# attac_decay_generator.net
KiCad netlist of a schematic drawn in Altium Designer
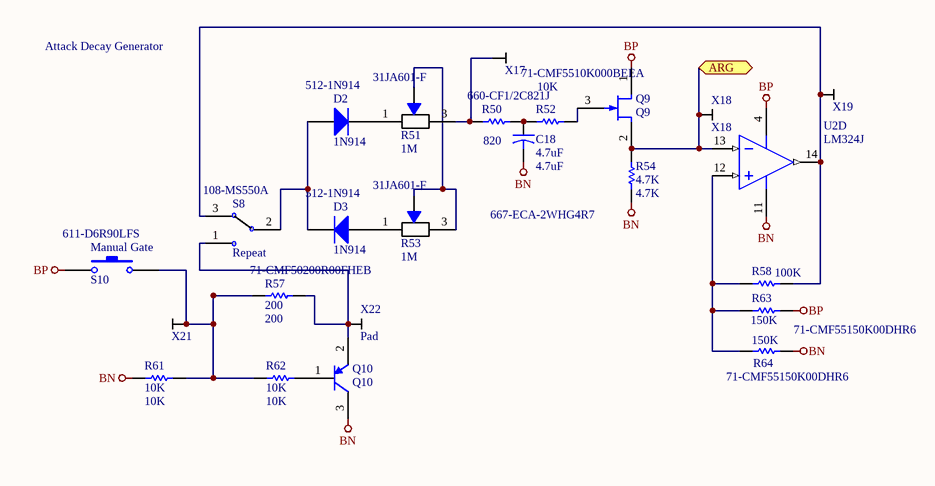
[diagram p0: attac_decay_generator.SchDoc]

(export (version "E")
  (design (tool "Eeschema 10.0.6"))
  (components
    (comp (ref "C18")
      (value "4.7uF")
      (footprint "CAPR5-4X5")
      (description "Capacitor")
      (fields
        (field (name "ALTIUM_VALUE") "4.7uF")
        (field (name "SUPPLIER PART NUMBER 1") "667-ECA-2WHG4R7")
        (field (name "MANUFACTURER") "Panasonic")
        (field (name "MANUFACTURER PART NUMBER") "ECA-2WHG4R7")
        (field (name "PUBLISHER") "Altium Limited")
      )
      (libsource (lib "Miscellaneous Devices") (part "Cap2"))
    )
    (comp (ref "D2")
      (value "1N914")
      (footprint "DO-35")
      (description "High Conductance Fast Diode")
      (fields
        (field (name "SUPPLIER PART NUMBER 1") "512-1N914")
        (field (name "MANUFACTURER") "ON Semiconductor / Fairchild")
        (field (name "PUBLISHER") "Altium Limited")
      )
      (libsource (lib "Miscellaneous Devices") (part "Diode 1N914"))
    )
    (comp (ref "D3")
      (value "1N914")
      (footprint "DO-35")
      (description "High Conductance Fast Diode")
      (fields
        (field (name "SUPPLIER PART NUMBER 1") "512-1N914")
        (field (name "MANUFACTURER") "ON Semiconductor / Fairchild")
        (field (name "PUBLISHER") "Altium Limited")
      )
      (libsource (lib "Miscellaneous Devices") (part "Diode 1N914"))
    )
    (comp (ref "Manual Gate")
      (value "S10")
      (footprint "SPST-2")
      (description "Switch")
      (fields
        (field (name "SUPPLIER PART NUMBER 1") "611-D6R90LFS")
        (field (name "MANUFACTURER") "C&K Components")
        (field (name "MANUFACTURER PART NUMBER") "D6R90 F1 LFS")
        (field (name "PUBLISHER") "Altium Limited")
      )
      (libsource (lib "Miscellaneous Devices") (part "SW-PB"))
    )
    (comp (ref "Q9")
      (value "Q9")
      (footprint "ONSC-SOT-23-3-318-08_V")
      (description "JFET Switching Transistor, N-Channel, 3-Pin SOT-23, Tape and Reel")
      (fields (field (name "MANUFACTURER") "On Semiconductor") (field (name "PARTNUMBER") "MMBF4391LT1"))
      (libsource (lib "ON Semi JFETs") (part "MMBF4391LT1"))
    )
    (comp (ref "Q10")
      (value "Q10")
      (footprint "ONSC-SC-75-3-463-01_V")
      (description "General Purpose Transistor, PNP Silicon, 3-Pin SC-75, Pb-Free, Tape and Reel")
      (fields (field (name "MANUFACTURER") "On Semiconductor") (field (name "PARTNUMBER") "MMBT3906TT1G"))
      (libsource (lib "ON Semi General Purpose Transistors") (part "MMBT3906TT1G"))
    )
    (comp (ref "R50")
      (value "820")
      (footprint "AXIAL-0.3")
      (description "Resistor")
      (fields
        (field (name "SUPPLIER PART NUMBER 1") "660-CF1/2C821J")
        (field (name "MANUFACTURER") "KOA Speer")
        (field (name "MANUFACTURER PART NUMBER") "CF1/2C821J")
        (field (name "PUBLISHER") "Altium Limited")
      )
      (libsource (lib "Miscellaneous Devices") (part "Res1"))
    )
    (comp (ref "R51")
      (value "1M")
      (footprint "Potentiometer")
      (description "My Own")
      (fields
        (field (name "SUPPLIER PART NUMBER 1") "31JA601-F")
        (field (name "MANUFACTURER") "Alpha (Taiwan)")
        (field (name "MANUFACTURER PART NUMBER") "RV16AF-10-20R1-A1M-LA")
      )
      (libsource (lib "MyLibrary") (part "Potentiometer"))
    )
    (comp (ref "R52")
      (value "10K")
      (footprint "AXIAL-0.3")
      (description "Metal Film Resistors - Through Hole 1/4watt 10Kohms 5% Rated to 1/2watt")
      (fields
        (field (name "MANUFACTURER") "Vishay / Dale")
        (field (name "MANUFACTURER PART NUMBER") "CCF0710K0JKE36")
        (field (name "SUPPLIER PART NUMBER 2") "71-CMF5510K000BEEA")
        (field (name "PUBLISHER") "Altium Limited")
      )
      (libsource (lib "Miscellaneous Devices") (part "Res1"))
    )
    (comp (ref "R53")
      (value "1M")
      (footprint "Potentiometer")
      (description "My Own")
      (fields
        (field (name "SUPPLIER PART NUMBER 1") "31JA601-F")
        (field (name "MANUFACTURER") "Alpha (Taiwan)")
        (field (name "MANUFACTURER PART NUMBER") "RV16AF-10-20R1-A1M-LA")
      )
      (libsource (lib "MyLibrary") (part "Potentiometer"))
    )
    (comp (ref "R54")
      (value "4.7K")
      (footprint "AXIAL-0.3")
      (description "Resistor")
      (fields
        (field (name "ALTIUM_VALUE") "4.7K")
        (field (name "MANUFACTURER") "Vishay / Dale")
        (field (name "MANUFACTURER PART NUMBER") "CCF074K70JKE36")
        (field (name "PUBLISHER") "Altium Limited")
      )
      (libsource (lib "Miscellaneous Devices") (part "Res1"))
    )
    (comp (ref "R57")
      (value "200")
      (footprint "AXIAL-0.3")
      (description "Resistor")
      (fields
        (field (name "ALTIUM_VALUE") "200")
        (field (name "SUPPLIER PART NUMBER 1") "71-CMF50200R00FHEB")
        (field (name "MANUFACTURER") "Vishay / Dale")
        (field (name "MANUFACTURER PART NUMBER") "CMF50200R00FHEB")
        (field (name "PUBLISHER") "Altium Limited")
      )
      (libsource (lib "Miscellaneous Devices") (part "Res1"))
    )
    (comp (ref "R58")
      (value "100K")
      (footprint "AXIAL-0.3")
      (description "Resistor")
      (fields
        (field (name "MANUFACTURER") "Vishay / Dale")
        (field (name "MANUFACTURER PART NUMBER") "CMF55100K00FHEK")
        (field (name "PUBLISHER") "Altium Limited")
      )
      (libsource (lib "Miscellaneous Devices") (part "Res1"))
    )
    (comp (ref "R61")
      (value "10K")
      (footprint "AXIAL-0.3")
      (description "Metal Film Resistors - Through Hole 1/4watt 10Kohms 5% Rated to 1/2watt")
      (fields
        (field (name "ALTIUM_VALUE") "10K")
        (field (name "MANUFACTURER") "Vishay / Dale")
        (field (name "MANUFACTURER PART NUMBER") "CCF0710K0JKE36")
        (field (name "PUBLISHER") "Altium Limited")
      )
      (libsource (lib "Miscellaneous Devices") (part "Res1"))
    )
    (comp (ref "R62")
      (value "10K")
      (footprint "AXIAL-0.3")
      (description "Metal Film Resistors - Through Hole 1/4watt 10Kohms 5% Rated to 1/2watt")
      (fields
        (field (name "ALTIUM_VALUE") "10K")
        (field (name "MANUFACTURER") "Vishay / Dale")
        (field (name "MANUFACTURER PART NUMBER") "CCF0710K0JKE36")
        (field (name "PUBLISHER") "Altium Limited")
      )
      (libsource (lib "Miscellaneous Devices") (part "Res1"))
    )
    (comp (ref "R63")
      (value "150K")
      (footprint "AXIAL-0.3")
      (description "Resistor")
      (fields
        (field (name "SUPPLIER PART NUMBER 1") "71-CMF55150K00DHR6")
        (field (name "MANUFACTURER") "Vishay / Dale")
        (field (name "MANUFACTURER PART NUMBER") "CMF55150K00DHR6")
        (field (name "PUBLISHER") "Altium Limited")
      )
      (libsource (lib "Miscellaneous Devices") (part "Res1"))
    )
    (comp (ref "R64")
      (value "150K")
      (footprint "AXIAL-0.3")
      (description "Resistor")
      (fields
        (field (name "SUPPLIER PART NUMBER 1") "71-CMF55150K00DHR6")
        (field (name "MANUFACTURER") "Vishay / Dale")
        (field (name "MANUFACTURER PART NUMBER") "CMF55150K00DHR6")
        (field (name "PUBLISHER") "Altium Limited")
      )
      (libsource (lib "Miscellaneous Devices") (part "Res1"))
    )
    (comp (ref "S8")
      (value "Repeat")
      (footprint "SPDT Switch")
      (description "SPDT Switch")
      (fields
        (field (name "SUPPLIER PART NUMBER 1") "108-MS550A")
        (field (name "MANUFACTURER") "Mountain Switch")
        (field (name "MANUFACTURER PART NUMBER") "108-MS550A")
      )
      (libsource (lib "MyLibrary") (part "SPDT Switch"))
    )
    (comp (ref "U2")
      (value "LM324J")
      (footprint "J14A")
      (description "Low Power Quad Operational Amplifier, 14-pin CerDIP")
      (fields (field (name "MANUFACTURER") "National Semiconductor"))
      (libsource (lib "National Semiconductor Amplifier") (part "LM324J"))
    )
    (comp (ref "X17") (value "X17") (footprint "Pad") (libsource (lib "MyLibrary") (part "Pad")))
    (comp (ref "X18") (value "X18") (footprint "Pad") (libsource (lib "MyLibrary") (part "Pad")))
    (comp (ref "X19") (value "X19") (footprint "Pad") (libsource (lib "MyLibrary") (part "Pad")))
    (comp (ref "X21") (value "X21") (footprint "Pad") (libsource (lib "MyLibrary") (part "Pad")))
    (comp (ref "X22") (value "Pad") (footprint "Pad") (libsource (lib "MyLibrary") (part "Pad")))
  )
  (nets
    (net (code "1") (name "/ARG") (class "Default")
      (node (ref "Q9") (pin "2") (pinfunction "S_2") (pintype "passive"))
      (node (ref "R54") (pin "2") (pinfunction "2_2") (pintype "passive"))
      (node (ref "U2") (pin "13") (pinfunction "IN4-_13") (pintype "input"))
      (node (ref "X18") (pin "1") (pinfunction "1_1") (pintype "passive"))
    )
    (net (code "2") (name "BN") (class "Default")
      (node (ref "C18") (pin "2") (pinfunction "2_2") (pintype "passive"))
      (node (ref "Q10") (pin "3") (pinfunction "C_3") (pintype "passive"))
      (node (ref "R54") (pin "1") (pinfunction "1_1") (pintype "passive"))
      (node (ref "R61") (pin "1") (pinfunction "1_1") (pintype "passive"))
      (node (ref "R64") (pin "2") (pinfunction "2_2") (pintype "passive"))
      (node (ref "U2") (pin "11") (pinfunction "GND_11") (pintype "power_in"))
    )
    (net (code "3") (name "BP") (class "Default")
      (node (ref "Manual Gate") (pin "1") (pinfunction "1_1") (pintype "passive"))
      (node (ref "Q9") (pin "1") (pinfunction "D_1") (pintype "passive"))
      (node (ref "R63") (pin "2") (pinfunction "2_2") (pintype "passive"))
      (node (ref "U2") (pin "4") (pinfunction "V+_4") (pintype "power_in"))
    )
    (net (code "4") (name "Net-(C18-Pad1)") (class "Default")
      (node (ref "C18") (pin "1") (pinfunction "1_1") (pintype "passive"))
      (node (ref "R50") (pin "2") (pinfunction "2_2") (pintype "passive"))
      (node (ref "R52") (pin "1") (pinfunction "1_1") (pintype "passive"))
    )
    (net (code "5") (name "Net-(D2-A)") (class "Default")
      (node (ref "D2") (pin "1") (pinfunction "A_1") (pintype "passive"))
      (node (ref "D3") (pin "2") (pinfunction "K_2") (pintype "passive"))
      (node (ref "S8") (pin "2") (pinfunction "2_2") (pintype "passive"))
    )
    (net (code "6") (name "Net-(D2-K)") (class "Default")
      (node (ref "D2") (pin "2") (pinfunction "K_2") (pintype "passive"))
      (node (ref "R51") (pin "1") (pinfunction "1_1") (pintype "passive"))
    )
    (net (code "7") (name "Net-(D3-A)") (class "Default")
      (node (ref "D3") (pin "1") (pinfunction "A_1") (pintype "passive"))
      (node (ref "R53") (pin "1") (pinfunction "1_1") (pintype "passive"))
    )
    (net (code "8") (name "Net-(Manual Gate-Pad2)") (class "Default")
      (node (ref "Manual Gate") (pin "2") (pinfunction "2_2") (pintype "passive"))
      (node (ref "R57") (pin "1") (pinfunction "1_1") (pintype "passive"))
      (node (ref "R61") (pin "2") (pinfunction "2_2") (pintype "passive"))
      (node (ref "R62") (pin "1") (pinfunction "1_1") (pintype "passive"))
      (node (ref "X21") (pin "1") (pinfunction "1_1") (pintype "passive"))
    )
    (net (code "9") (name "Net-(Q9-G)") (class "Default")
      (node (ref "Q9") (pin "3") (pinfunction "G_3") (pintype "passive"))
      (node (ref "R52") (pin "2") (pinfunction "2_2") (pintype "passive"))
    )
    (net (code "10") (name "Net-(Q10-B)") (class "Default")
      (node (ref "Q10") (pin "1") (pinfunction "B_1") (pintype "passive"))
      (node (ref "R62") (pin "2") (pinfunction "2_2") (pintype "passive"))
    )
    (net (code "11") (name "Net-(Q10-E)") (class "Default")
      (node (ref "Q10") (pin "2") (pinfunction "E_2") (pintype "passive"))
      (node (ref "R57") (pin "2") (pinfunction "2_2") (pintype "passive"))
      (node (ref "S8") (pin "1") (pinfunction "1_1") (pintype "passive"))
      (node (ref "X22") (pin "1") (pinfunction "1_1") (pintype "passive"))
    )
    (net (code "12") (name "Net-(R50-Pad1)") (class "Default")
      (node (ref "R50") (pin "1") (pinfunction "1_1") (pintype "passive"))
      (node (ref "R51") (pin "3") (pinfunction "3_3") (pintype "passive"))
      (node (ref "X17") (pin "1") (pinfunction "1_1") (pintype "passive"))
    )
    (net (code "13") (name "Net-(R51-Pad2)") (class "Default")
      (node (ref "R51") (pin "2") (pinfunction "2_2") (pintype "passive"))
      (node (ref "R53") (pin "2") (pinfunction "2_2") (pintype "passive"))
      (node (ref "R53") (pin "3") (pinfunction "3_3") (pintype "passive"))
    )
    (net (code "14") (name "Net-(U2D-IN4+)") (class "Default")
      (node (ref "R58") (pin "1") (pinfunction "1_1") (pintype "passive"))
      (node (ref "R63") (pin "1") (pinfunction "1_1") (pintype "passive"))
      (node (ref "R64") (pin "1") (pinfunction "1_1") (pintype "passive"))
      (node (ref "U2") (pin "12") (pinfunction "IN4+_12") (pintype "input"))
    )
    (net (code "15") (name "Net-(U2D-OUT4)") (class "Default")
      (node (ref "R58") (pin "2") (pinfunction "2_2") (pintype "passive"))
      (node (ref "S8") (pin "3") (pinfunction "3_3") (pintype "passive"))
      (node (ref "U2") (pin "14") (pinfunction "OUT4_14") (pintype "output"))
      (node (ref "X19") (pin "1") (pinfunction "1_1") (pintype "passive"))
    )
  )
)
